# Jacks.net
KiCad netlist of a schematic drawn in Altium Designer
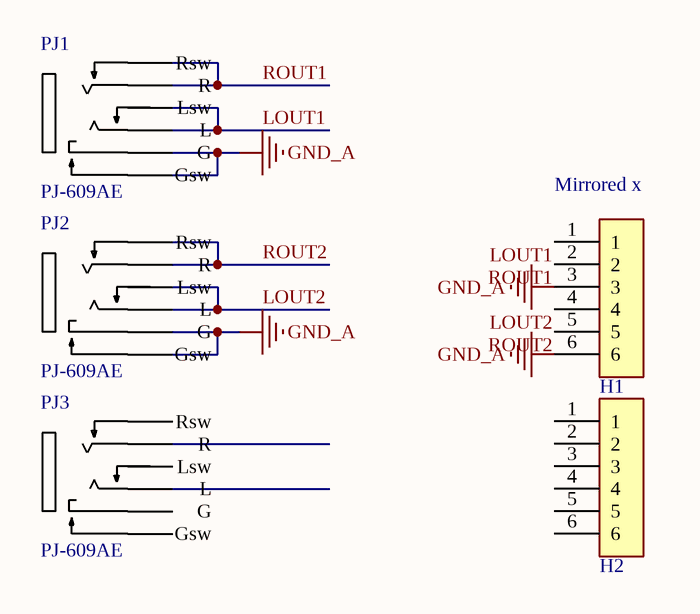
[diagram p0: Jacks.SchDoc]

(export (version "E")
  (design (tool "Eeschema 10.0.6"))
  (components
    (comp (ref "H1")
      (value "1.5-6A")
      (footprint "ProtoStack_H750VBT:1.5-6A")
      (description "Pin Header p=1.5mm, 6 pins")
      (libsource (lib "ProtoStack_H750VBT") (part "1.5-6A"))
    )
    (comp (ref "H2")
      (value "1.5-6A")
      (footprint "ProtoStack_H750VBT:1.5-6A")
      (description "Pin Header p=1.5mm, 6 pins")
      (libsource (lib "ProtoStack_H750VBT") (part "1.5-6A"))
    )
    (comp (ref "PJ1")
      (value "PJ-609AE")
      (footprint "ProtoStack_H750VBT:PJ609AE")
      (description "6.3mm jack HOOYA")
      (libsource (lib "ProtoStack_H750VBT") (part "PJ-609AE"))
    )
    (comp (ref "PJ2")
      (value "PJ-609AE")
      (footprint "ProtoStack_H750VBT:PJ609AE")
      (description "6.3mm jack HOOYA")
      (libsource (lib "ProtoStack_H750VBT") (part "PJ-609AE"))
    )
    (comp (ref "PJ3")
      (value "PJ-609AE")
      (footprint "ProtoStack_H750VBT:PJ609AE")
      (description "6.3mm jack HOOYA")
      (libsource (lib "ProtoStack_H750VBT") (part "PJ-609AE"))
    )
  )
  (nets
    (net (code "1") (name "/LOUT1") (class "Default")
      (node (ref "H1") (pin "1") (pinfunction "1_1") (pintype "passive"))
      (node (ref "PJ1") (pin "6") (pinfunction "L_6") (pintype "passive"))
      (node (ref "PJ1") (pin "7") (pinfunction "Lsw_7") (pintype "passive"))
    )
    (net (code "2") (name "/LOUT2") (class "Default")
      (node (ref "H1") (pin "4") (pinfunction "4_4") (pintype "passive"))
      (node (ref "PJ2") (pin "6") (pinfunction "L_6") (pintype "passive"))
      (node (ref "PJ2") (pin "7") (pinfunction "Lsw_7") (pintype "passive"))
    )
    (net (code "3") (name "/ROUT1") (class "Default")
      (node (ref "H1") (pin "2") (pinfunction "2_2") (pintype "passive"))
      (node (ref "PJ1") (pin "4") (pinfunction "R_4") (pintype "passive"))
      (node (ref "PJ1") (pin "5") (pinfunction "Rsw_5") (pintype "passive"))
    )
    (net (code "4") (name "/ROUT2") (class "Default")
      (node (ref "H1") (pin "5") (pinfunction "5_5") (pintype "passive"))
      (node (ref "PJ2") (pin "4") (pinfunction "R_4") (pintype "passive"))
      (node (ref "PJ2") (pin "5") (pinfunction "Rsw_5") (pintype "passive"))
    )
    (net (code "5") (name "GND_A") (class "Default")
      (node (ref "H1") (pin "3") (pinfunction "3_3") (pintype "passive"))
      (node (ref "H1") (pin "6") (pinfunction "6_6") (pintype "passive"))
      (node (ref "PJ1") (pin "2") (pinfunction "G_2") (pintype "passive"))
      (node (ref "PJ1") (pin "3") (pinfunction "Gsw_3") (pintype "passive"))
      (node (ref "PJ2") (pin "2") (pinfunction "G_2") (pintype "passive"))
      (node (ref "PJ2") (pin "3") (pinfunction "Gsw_3") (pintype "passive"))
    )
    (net (code "6") (name "unconnected-(H2-Pad1)") (class "Default")
      (node (ref "H2") (pin "1") (pinfunction "1_1") (pintype "passive"))
    )
    (net (code "7") (name "unconnected-(H2-Pad2)") (class "Default")
      (node (ref "H2") (pin "2") (pinfunction "2_2") (pintype "passive"))
    )
    (net (code "8") (name "unconnected-(H2-Pad3)") (class "Default")
      (node (ref "H2") (pin "3") (pinfunction "3_3") (pintype "passive"))
    )
    (net (code "9") (name "unconnected-(H2-Pad4)") (class "Default")
      (node (ref "H2") (pin "4") (pinfunction "4_4") (pintype "passive"))
    )
    (net (code "10") (name "unconnected-(H2-Pad5)") (class "Default")
      (node (ref "H2") (pin "5") (pinfunction "5_5") (pintype "passive"))
    )
    (net (code "11") (name "unconnected-(H2-Pad6)") (class "Default")
      (node (ref "H2") (pin "6") (pinfunction "6_6") (pintype "passive"))
    )
    (net (code "12") (name "unconnected-(PJ3-G-Pad2)") (class "Default")
      (node (ref "PJ3") (pin "2") (pinfunction "G_2") (pintype "passive"))
    )
    (net (code "13") (name "unconnected-(PJ3-Gsw-Pad3)") (class "Default")
      (node (ref "PJ3") (pin "3") (pinfunction "Gsw_3") (pintype "passive"))
    )
    (net (code "14") (name "unconnected-(PJ3-L-Pad6)") (class "Default")
      (node (ref "PJ3") (pin "6") (pinfunction "L_6") (pintype "passive"))
    )
    (net (code "15") (name "unconnected-(PJ3-Lsw-Pad7)") (class "Default")
      (node (ref "PJ3") (pin "7") (pinfunction "Lsw_7") (pintype "passive"))
    )
    (net (code "16") (name "unconnected-(PJ3-R-Pad4)") (class "Default")
      (node (ref "PJ3") (pin "4") (pinfunction "R_4") (pintype "passive"))
    )
    (net (code "17") (name "unconnected-(PJ3-Rsw-Pad5)") (class "Default")
      (node (ref "PJ3") (pin "5") (pinfunction "Rsw_5") (pintype "passive"))
    )
  )
)
